# Stepping_Motor_DriverA.net
KiCad netlist of a schematic drawn in Altium Designer
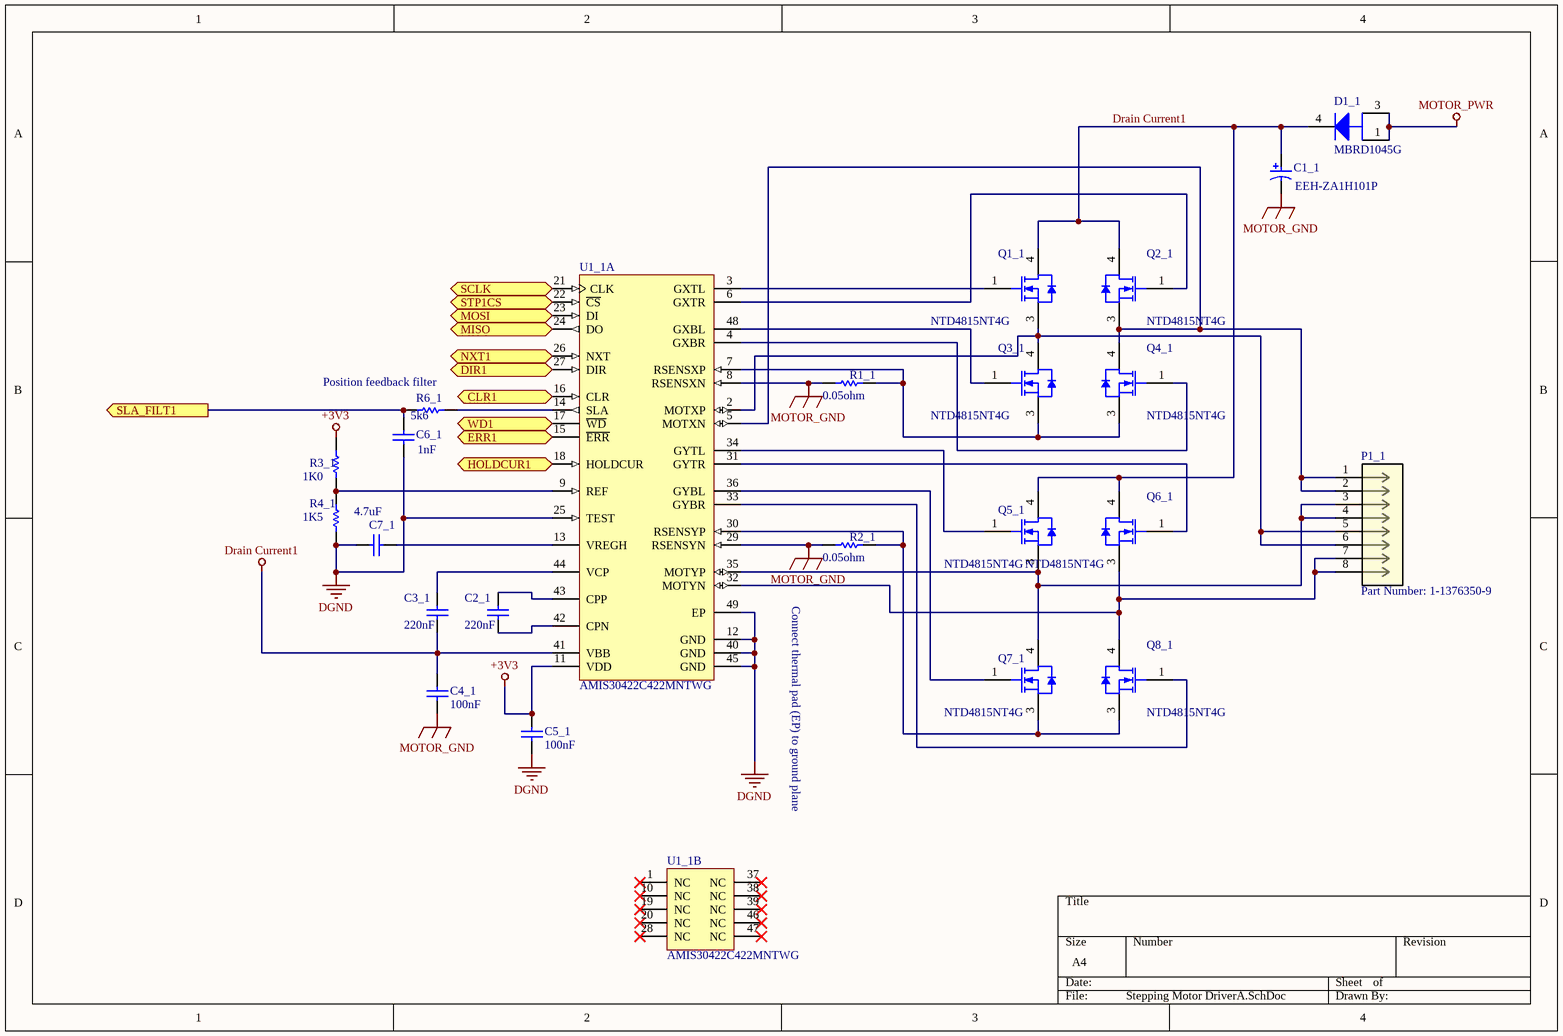
[diagram p0: Stepping Motor DriverA.SchDoc]

(export (version "E")
  (design (tool "Eeschema 10.0.6"))
  (components
    (comp (ref "C1_1")
      (value "EEH-ZA1H101P")
      (footprint "PNSC-ZA-G_L")
      (fields (field (name "TOLERANCE") "20%") (field (name "MANUFACTURER") "Panasonic"))
      (libsource (lib "Altium Content Vault") (part "CAP-P-2"))
    )
    (comp (ref "C2_1")
      (value "220nF")
      (footprint "CAPC0805(2012)75_L")
      (description "CAP 220nF 50V -20% to +80% 0805 (2012 Metric) Thickness 0.75mm SMD")
      (fields (field (name "TOLERANCE") "-20% to +80%") (field (name "Comment") "CAP 220nF 50V 0805(2012)"))
      (libsource (lib "Altium Content Vault") (part "CMP-1036-04556-1"))
    )
    (comp (ref "C3_1")
      (value "220nF")
      (footprint "CAPC0805(2012)75_L")
      (description "CAP 220nF 50V -20% to +80% 0805 (2012 Metric) Thickness 0.75mm SMD")
      (fields (field (name "TOLERANCE") "-20% to +80%") (field (name "Comment") "CAP 220nF 50V 0805(2012)"))
      (libsource (lib "Altium Content Vault") (part "CMP-1036-04556-1"))
    )
    (comp (ref "C4_1")
      (value "100nF")
      (footprint "CAPC1812(4532)110_N")
      (description "CAP 100nF 50V ±20% 1812 (4532 Metric) Thickness 1.1mm SMD")
      (fields (field (name "TOLERANCE") "Â±20%") (field (name "Comment") "CAP 100nF 50V 1812(4532)"))
      (libsource (lib "Altium Content Vault") (part "CMP-1040-01292-1"))
    )
    (comp (ref "C5_1")
      (value "100nF")
      (footprint "CAPC1812(4532)110_N")
      (description "CAP 100nF 50V ±20% 1812 (4532 Metric) Thickness 1.1mm SMD")
      (fields (field (name "TOLERANCE") "Â±20%") (field (name "Comment") "CAP 100nF 50V 1812(4532)"))
      (libsource (lib "Altium Content Vault") (part "CMP-1040-01292-1"))
    )
    (comp (ref "C6_1")
      (value "1nF")
      (footprint "CAPC1206(3216)170_N")
      (description "CAP 1nF 50V ±2% 1206 (3216 Metric) Thickness 1.7mm SMD")
      (fields (field (name "TOLERANCE") "Â±2%") (field (name "Comment") "CAP 1nF 50V 1206(3216)"))
      (libsource (lib "Altium Content Vault") (part "CMP-1037-02447-1"))
    )
    (comp (ref "C7_1")
      (value "4.7uF")
      (footprint "CAPC2220(5750)230_L")
      (description "CAP 4.7uF 50V ±10% 2220 (5750 Metric) Thickness 2.2mm SMD")
      (fields (field (name "TOLERANCE") "Â±10%") (field (name "Comment") "CAP 4.7uF 50V 2220(5750)"))
      (libsource (lib "Altium Content Vault") (part "CMP-1042-00755-1"))
    )
    (comp (ref "D1_1")
      (value "MBRD1045G")
      (footprint "ONSC-DPAK-3-369C-01_V")
      (description "SWITCHMODE(TM) Schottky Power Rectifier, 3-Pin DPAK, Pb-Free, Tube")
      (fields (field (name "MANUFACTURER") "On Semiconductor"))
      (libsource (lib "Altium Content Vault") (part "ONSC-D-A1A3K4-3_A"))
    )
    (comp (ref "P1_1")
      (value "Part Number: 1-1376350-9")
      (footprint "conn8_1-1376350-")
      (description "025 8POS CAP ASSY H TIN")
      (fields
        (field (name "MANUFACTURER_PART_NUMBER") "1-1376350-9")
        (field (name "COPYRIGHT") "Copyright (C) 2018 Accelerated Designs. All rights reserved")
      )
      (libsource (lib "2020-04-08_04-40-03") (part "1-1376350-9"))
    )
    (comp (ref "Q1_1")
      (value "NTD4815NT4G")
      (footprint "ONSC-DPAK-3-369AA-01_V")
      (description "Power MOSFET, 30 V, 35 A, Single N-Channel, 3-Pin DPAK, Pb-Free, Tape and Reel")
      (fields (field (name "MANUFACTURER") "On Semiconductor"))
      (libsource (lib "Altium Content Vault") (part "CMP-1058-00298-1"))
    )
    (comp (ref "Q2_1")
      (value "NTD4815NT4G")
      (footprint "ONSC-DPAK-3-369AA-01_V")
      (description "Power MOSFET, 30 V, 35 A, Single N-Channel, 3-Pin DPAK, Pb-Free, Tape and Reel")
      (fields (field (name "MANUFACTURER") "On Semiconductor"))
      (libsource (lib "Altium Content Vault") (part "CMP-1058-00298-1"))
    )
    (comp (ref "Q3_1")
      (value "NTD4815NT4G")
      (footprint "ONSC-DPAK-3-369AA-01_V")
      (description "Power MOSFET, 30 V, 35 A, Single N-Channel, 3-Pin DPAK, Pb-Free, Tape and Reel")
      (fields (field (name "MANUFACTURER") "On Semiconductor"))
      (libsource (lib "Altium Content Vault") (part "ONSC-NMOS-G1S3D4-3_B"))
    )
    (comp (ref "Q4_1")
      (value "NTD4815NT4G")
      (footprint "ONSC-DPAK-3-369AA-01_V")
      (description "Power MOSFET, 30 V, 35 A, Single N-Channel, 3-Pin DPAK, Pb-Free, Tape and Reel")
      (fields (field (name "MANUFACTURER") "On Semiconductor"))
      (libsource (lib "Altium Content Vault") (part "CMP-1058-00298-1"))
    )
    (comp (ref "Q5_1")
      (value "NTD4815NT4G")
      (footprint "ONSC-DPAK-3-369AA-01_V")
      (description "Power MOSFET, 30 V, 35 A, Single N-Channel, 3-Pin DPAK, Pb-Free, Tape and Reel")
      (fields (field (name "MANUFACTURER") "On Semiconductor"))
      (libsource (lib "Altium Content Vault") (part "ONSC-NMOS-G1S3D4-3_B"))
    )
    (comp (ref "Q6_1")
      (value "NTD4815NT4G")
      (footprint "ONSC-DPAK-3-369AA-01_V")
      (description "Power MOSFET, 30 V, 35 A, Single N-Channel, 3-Pin DPAK, Pb-Free, Tape and Reel")
      (fields (field (name "MANUFACTURER") "On Semiconductor"))
      (libsource (lib "Altium Content Vault") (part "CMP-1058-00298-1"))
    )
    (comp (ref "Q7_1")
      (value "NTD4815NT4G")
      (footprint "ONSC-DPAK-3-369AA-01_V")
      (description "Power MOSFET, 30 V, 35 A, Single N-Channel, 3-Pin DPAK, Pb-Free, Tape and Reel")
      (fields (field (name "MANUFACTURER") "On Semiconductor"))
      (libsource (lib "Altium Content Vault") (part "ONSC-NMOS-G1S3D4-3_B"))
    )
    (comp (ref "Q8_1")
      (value "NTD4815NT4G")
      (footprint "ONSC-DPAK-3-369AA-01_V")
      (description "Power MOSFET, 30 V, 35 A, Single N-Channel, 3-Pin DPAK, Pb-Free, Tape and Reel")
      (fields (field (name "MANUFACTURER") "On Semiconductor"))
      (libsource (lib "Altium Content Vault") (part "CMP-1058-00298-1"))
    )
    (comp (ref "R1_1")
      (value "WSL2512R0500FEA")
      (footprint "RESC6432X89X76LL25T25")
      (description "Chip Resistor, 50 mOhm, +/- 1%, 1 W, -65 to 170 degC, 2512 (6432 Metric), RoHS, Tape and Reel")
      (fields (field (name "MANUFACTURER") "Vishay") (field (name "RESISTANCE") "0.05ohm"))
      (libsource (lib "Altium Content Vault") (part "CMP-2000-07420-1"))
    )
    (comp (ref "R2_1")
      (value "WSL2512R0500FEA")
      (footprint "RESC6432X89X76LL25T25")
      (description "Chip Resistor, 50 mOhm, +/- 1%, 1 W, -65 to 170 degC, 2512 (6432 Metric), RoHS, Tape and Reel")
      (fields (field (name "MANUFACTURER") "Vishay") (field (name "RESISTANCE") "0.05ohm"))
      (libsource (lib "Altium Content Vault") (part "CMP-2000-07420-1"))
    )
    (comp (ref "R3_1")
      (value "1K0")
      (footprint "RESC0805(2012)_M")
      (description "1K 0.125W 1% 0805 (2012 Metric)  SMD")
      (fields (field (name "TOLERANCE") "1 %") (field (name "POWER") "0.125 W"))
      (libsource (lib "Altium Content Vault") (part "CMP-1013-00510-1"))
    )
    (comp (ref "R4_1")
      (value "1K5")
      (footprint "RESC0805(2012)_M")
      (description "1K5 0.125W 1% 0805 (2012 Metric)  SMD")
      (fields (field (name "POWER") "0.125 W") (field (name "TOLERANCE") "1 %"))
      (libsource (lib "Altium Content Vault") (part "CMP-1013-00528-1"))
    )
    (comp (ref "R6_1")
      (value "5k6")
      (footprint "RESC0805(2012)_L")
      (description "5K6 0.125W 1% 0805 (2012 Metric)  SMD")
      (fields (field (name "POWER") "0.125 W") (field (name "TOLERANCE") "1 %"))
      (libsource (lib "Altium Content Vault") (part "CMP-1013-00595-1"))
    )
    (comp (ref "U1_1")
      (value "AMIS30422C422MNTWG")
      (footprint "ONSC-QFN-48-485AJ-01_V")
      (fields (field (name "MANUFACTURER") "ON Semiconductor"))
      (libsource (lib "Altium Content Vault") (part "ONSC-AMIS-30422-QFN-48"))
    )
  )
  (nets
    (net (code "1") (name "+3V3") (class "Default")
      (node (ref "C5_1") (pin "2") (pinfunction "2_2") (pintype "passive"))
      (node (ref "R3_1") (pin "2") (pinfunction "2_2") (pintype "passive"))
      (node (ref "U1_1") (pin "11") (pinfunction "VDD_11") (pintype "power_in"))
    )
    (net (code "2") (name "/CLR1") (class "Default")
      (node (ref "U1_1") (pin "16") (pinfunction "CLR_16") (pintype "input"))
    )
    (net (code "3") (name "/DIR1") (class "Default")
      (node (ref "U1_1") (pin "27") (pinfunction "DIR_27") (pintype "input"))
    )
    (net (code "4") (name "/ERR1") (class "Default")
      (node (ref "U1_1") (pin "15") (pinfunction "~{ERR}_15") (pintype "tri_state"))
    )
    (net (code "5") (name "/HOLDCUR1") (class "Default")
      (node (ref "U1_1") (pin "18") (pinfunction "HOLDCUR_18") (pintype "input"))
    )
    (net (code "6") (name "/MISO") (class "Default")
      (node (ref "U1_1") (pin "24") (pinfunction "DO_24") (pintype "output"))
    )
    (net (code "7") (name "/MOSI") (class "Default")
      (node (ref "U1_1") (pin "23") (pinfunction "DI_23") (pintype "input"))
    )
    (net (code "8") (name "/NXT1") (class "Default")
      (node (ref "U1_1") (pin "26") (pinfunction "NXT_26") (pintype "input"))
    )
    (net (code "9") (name "/SCLK") (class "Default")
      (node (ref "U1_1") (pin "21") (pinfunction "CLK_21") (pintype "input"))
    )
    (net (code "10") (name "/SLA_FILT1") (class "Default")
      (node (ref "C6_1") (pin "2") (pinfunction "2_2") (pintype "passive"))
      (node (ref "R6_1") (pin "1") (pinfunction "1_1") (pintype "passive"))
    )
    (net (code "11") (name "/STP1CS") (class "Default")
      (node (ref "U1_1") (pin "22") (pinfunction "~{CS}_22") (pintype "input"))
    )
    (net (code "12") (name "/WD1") (class "Default")
      (node (ref "U1_1") (pin "17") (pinfunction "~{WD}_17") (pintype "tri_state"))
    )
    (net (code "13") (name "DGND") (class "Default")
      (node (ref "C5_1") (pin "1") (pinfunction "1_1") (pintype "passive"))
      (node (ref "C6_1") (pin "1") (pinfunction "1_1") (pintype "passive"))
      (node (ref "C7_1") (pin "1") (pinfunction "1_1") (pintype "passive"))
      (node (ref "R4_1") (pin "1") (pinfunction "1_1") (pintype "passive"))
      (node (ref "U1_1") (pin "12") (pinfunction "GND_12") (pintype "power_in"))
      (node (ref "U1_1") (pin "25") (pinfunction "TEST_25") (pintype "input"))
      (node (ref "U1_1") (pin "40") (pinfunction "GND_40") (pintype "power_in"))
      (node (ref "U1_1") (pin "45") (pinfunction "GND_45") (pintype "power_in"))
      (node (ref "U1_1") (pin "49") (pinfunction "EP_49") (pintype "passive"))
    )
    (net (code "14") (name "Drain Current1") (class "Default")
      (node (ref "C1_1") (pin "1") (pinfunction "1_1") (pintype "passive"))
      (node (ref "C3_1") (pin "1") (pinfunction "1_1") (pintype "passive"))
      (node (ref "C4_1") (pin "2") (pinfunction "2_2") (pintype "passive"))
      (node (ref "D1_1") (pin "4") (pinfunction "K_4") (pintype "passive"))
      (node (ref "Q1_1") (pin "4") (pinfunction "D_4") (pintype "passive"))
      (node (ref "Q2_1") (pin "4") (pinfunction "D_4") (pintype "passive"))
      (node (ref "Q5_1") (pin "4") (pinfunction "D_4") (pintype "passive"))
      (node (ref "Q6_1") (pin "4") (pinfunction "D_4") (pintype "passive"))
      (node (ref "U1_1") (pin "41") (pinfunction "VBB_41") (pintype "power_in"))
    )
    (net (code "15") (name "MOTOR_GND") (class "Default")
      (node (ref "C1_1") (pin "2") (pinfunction "2_2") (pintype "passive"))
      (node (ref "C4_1") (pin "1") (pinfunction "1_1") (pintype "passive"))
      (node (ref "R1_1") (pin "1") (pinfunction "1_1") (pintype "passive"))
      (node (ref "R2_1") (pin "1") (pinfunction "1_1") (pintype "passive"))
      (node (ref "U1_1") (pin "29") (pinfunction "RSENSYN_29") (pintype "input"))
      (node (ref "U1_1") (pin "8") (pinfunction "RSENSXN_8") (pintype "input"))
    )
    (net (code "16") (name "MOTOR_PWR") (class "Default")
      (node (ref "D1_1") (pin "1") (pinfunction "A_1") (pintype "passive"))
      (node (ref "D1_1") (pin "3") (pinfunction "A_3") (pintype "passive"))
    )
    (net (code "17") (name "Net-(Q1_1-G)") (class "Default")
      (node (ref "Q1_1") (pin "1") (pinfunction "G_1") (pintype "passive"))
      (node (ref "U1_1") (pin "3") (pinfunction "GXTL_3") (pintype "tri_state"))
    )
    (net (code "18") (name "Net-(Q1_1-S)") (class "Default")
      (node (ref "P1_1") (pin "5") (pinfunction "5_5") (pintype "passive"))
      (node (ref "P1_1") (pin "6") (pinfunction "6_6") (pintype "passive"))
      (node (ref "Q1_1") (pin "3") (pinfunction "S_3") (pintype "passive"))
      (node (ref "Q3_1") (pin "4") (pinfunction "D_4") (pintype "passive"))
      (node (ref "U1_1") (pin "2") (pinfunction "MOTXP_2") (pintype "bidirectional"))
    )
    (net (code "19") (name "Net-(Q2_1-G)") (class "Default")
      (node (ref "Q2_1") (pin "1") (pinfunction "G_1") (pintype "passive"))
      (node (ref "U1_1") (pin "6") (pinfunction "GXTR_6") (pintype "tri_state"))
    )
    (net (code "20") (name "Net-(Q2_1-S)") (class "Default")
      (node (ref "P1_1") (pin "1") (pinfunction "1_1") (pintype "passive"))
      (node (ref "P1_1") (pin "2") (pinfunction "2_2") (pintype "passive"))
      (node (ref "Q2_1") (pin "3") (pinfunction "S_3") (pintype "passive"))
      (node (ref "Q4_1") (pin "4") (pinfunction "D_4") (pintype "passive"))
      (node (ref "U1_1") (pin "5") (pinfunction "MOTXN_5") (pintype "bidirectional"))
    )
    (net (code "21") (name "Net-(Q3_1-G)") (class "Default")
      (node (ref "Q3_1") (pin "1") (pinfunction "G_1") (pintype "passive"))
      (node (ref "U1_1") (pin "48") (pinfunction "GXBL_48") (pintype "tri_state"))
    )
    (net (code "22") (name "Net-(Q3_1-S)") (class "Default")
      (node (ref "Q3_1") (pin "3") (pinfunction "S_3") (pintype "passive"))
      (node (ref "Q4_1") (pin "3") (pinfunction "S_3") (pintype "passive"))
      (node (ref "R1_1") (pin "2") (pinfunction "2_2") (pintype "passive"))
      (node (ref "U1_1") (pin "7") (pinfunction "RSENSXP_7") (pintype "input"))
    )
    (net (code "23") (name "Net-(Q4_1-G)") (class "Default")
      (node (ref "Q4_1") (pin "1") (pinfunction "G_1") (pintype "passive"))
      (node (ref "U1_1") (pin "4") (pinfunction "GXBR_4") (pintype "tri_state"))
    )
    (net (code "24") (name "Net-(Q5_1-G)") (class "Default")
      (node (ref "Q5_1") (pin "1") (pinfunction "G_1") (pintype "passive"))
      (node (ref "U1_1") (pin "34") (pinfunction "GYTL_34") (pintype "tri_state"))
    )
    (net (code "25") (name "Net-(Q5_1-S)") (class "Default")
      (node (ref "P1_1") (pin "3") (pinfunction "3_3") (pintype "passive"))
      (node (ref "P1_1") (pin "4") (pinfunction "4_4") (pintype "passive"))
      (node (ref "Q5_1") (pin "3") (pinfunction "S_3") (pintype "passive"))
      (node (ref "Q7_1") (pin "4") (pinfunction "D_4") (pintype "passive"))
      (node (ref "U1_1") (pin "35") (pinfunction "MOTYP_35") (pintype "bidirectional"))
    )
    (net (code "26") (name "Net-(Q6_1-G)") (class "Default")
      (node (ref "Q6_1") (pin "1") (pinfunction "G_1") (pintype "passive"))
      (node (ref "U1_1") (pin "31") (pinfunction "GYTR_31") (pintype "tri_state"))
    )
    (net (code "27") (name "Net-(Q6_1-S)") (class "Default")
      (node (ref "P1_1") (pin "7") (pinfunction "7_7") (pintype "passive"))
      (node (ref "P1_1") (pin "8") (pinfunction "8_8") (pintype "passive"))
      (node (ref "Q6_1") (pin "3") (pinfunction "S_3") (pintype "passive"))
      (node (ref "Q8_1") (pin "4") (pinfunction "D_4") (pintype "passive"))
      (node (ref "U1_1") (pin "32") (pinfunction "MOTYN_32") (pintype "bidirectional"))
    )
    (net (code "28") (name "Net-(Q7_1-G)") (class "Default")
      (node (ref "Q7_1") (pin "1") (pinfunction "G_1") (pintype "passive"))
      (node (ref "U1_1") (pin "36") (pinfunction "GYBL_36") (pintype "tri_state"))
    )
    (net (code "29") (name "Net-(Q7_1-S)") (class "Default")
      (node (ref "Q7_1") (pin "3") (pinfunction "S_3") (pintype "passive"))
      (node (ref "Q8_1") (pin "3") (pinfunction "S_3") (pintype "passive"))
      (node (ref "R2_1") (pin "2") (pinfunction "2_2") (pintype "passive"))
      (node (ref "U1_1") (pin "30") (pinfunction "RSENSYP_30") (pintype "input"))
    )
    (net (code "30") (name "Net-(Q8_1-G)") (class "Default")
      (node (ref "Q8_1") (pin "1") (pinfunction "G_1") (pintype "passive"))
      (node (ref "U1_1") (pin "33") (pinfunction "GYBR_33") (pintype "tri_state"))
    )
    (net (code "31") (name "Net-(U1_1A-CPN)") (class "Default")
      (node (ref "C2_1") (pin "1") (pinfunction "1_1") (pintype "passive"))
      (node (ref "U1_1") (pin "42") (pinfunction "CPN_42") (pintype "passive"))
    )
    (net (code "32") (name "Net-(U1_1A-CPP)") (class "Default")
      (node (ref "C2_1") (pin "2") (pinfunction "2_2") (pintype "passive"))
      (node (ref "U1_1") (pin "43") (pinfunction "CPP_43") (pintype "passive"))
    )
    (net (code "33") (name "Net-(U1_1A-REF)") (class "Default")
      (node (ref "R3_1") (pin "1") (pinfunction "1_1") (pintype "passive"))
      (node (ref "R4_1") (pin "2") (pinfunction "2_2") (pintype "passive"))
      (node (ref "U1_1") (pin "9") (pinfunction "REF_9") (pintype "input"))
    )
    (net (code "34") (name "Net-(U1_1A-SLA)") (class "Default")
      (node (ref "R6_1") (pin "2") (pinfunction "2_2") (pintype "passive"))
      (node (ref "U1_1") (pin "14") (pinfunction "SLA_14") (pintype "output"))
    )
    (net (code "35") (name "Net-(U1_1A-VCP)") (class "Default")
      (node (ref "C3_1") (pin "2") (pinfunction "2_2") (pintype "passive"))
      (node (ref "U1_1") (pin "44") (pinfunction "VCP_44") (pintype "passive"))
    )
    (net (code "36") (name "Net-(U1_1A-VREGH)") (class "Default")
      (node (ref "C7_1") (pin "2") (pinfunction "2_2") (pintype "passive"))
      (node (ref "U1_1") (pin "13") (pinfunction "VREGH_13") (pintype "power_in"))
    )
    (net (code "37") (name "unconnected-(U1_1B-NC-Pad1)") (class "Default")
      (node (ref "U1_1") (pin "1") (pinfunction "NC_1") (pintype "passive+no_connect"))
    )
    (net (code "38") (name "unconnected-(U1_1B-NC-Pad10)") (class "Default")
      (node (ref "U1_1") (pin "10") (pinfunction "NC_10") (pintype "passive+no_connect"))
    )
    (net (code "39") (name "unconnected-(U1_1B-NC-Pad19)") (class "Default")
      (node (ref "U1_1") (pin "19") (pinfunction "NC_19") (pintype "passive+no_connect"))
    )
    (net (code "40") (name "unconnected-(U1_1B-NC-Pad20)") (class "Default")
      (node (ref "U1_1") (pin "20") (pinfunction "NC_20") (pintype "passive+no_connect"))
    )
    (net (code "41") (name "unconnected-(U1_1B-NC-Pad28)") (class "Default")
      (node (ref "U1_1") (pin "28") (pinfunction "NC_28") (pintype "passive+no_connect"))
    )
    (net (code "42") (name "unconnected-(U1_1B-NC-Pad37)") (class "Default")
      (node (ref "U1_1") (pin "37") (pinfunction "NC_37") (pintype "passive+no_connect"))
    )
    (net (code "43") (name "unconnected-(U1_1B-NC-Pad38)") (class "Default")
      (node (ref "U1_1") (pin "38") (pinfunction "NC_38") (pintype "passive+no_connect"))
    )
    (net (code "44") (name "unconnected-(U1_1B-NC-Pad39)") (class "Default")
      (node (ref "U1_1") (pin "39") (pinfunction "NC_39") (pintype "passive+no_connect"))
    )
    (net (code "45") (name "unconnected-(U1_1B-NC-Pad46)") (class "Default")
      (node (ref "U1_1") (pin "46") (pinfunction "NC_46") (pintype "passive+no_connect"))
    )
    (net (code "46") (name "unconnected-(U1_1B-NC-Pad47)") (class "Default")
      (node (ref "U1_1") (pin "47") (pinfunction "NC_47") (pintype "passive+no_connect"))
    )
  )
)
